# Leddriver.net
KiCad netlist of a schematic drawn in Altium Designer
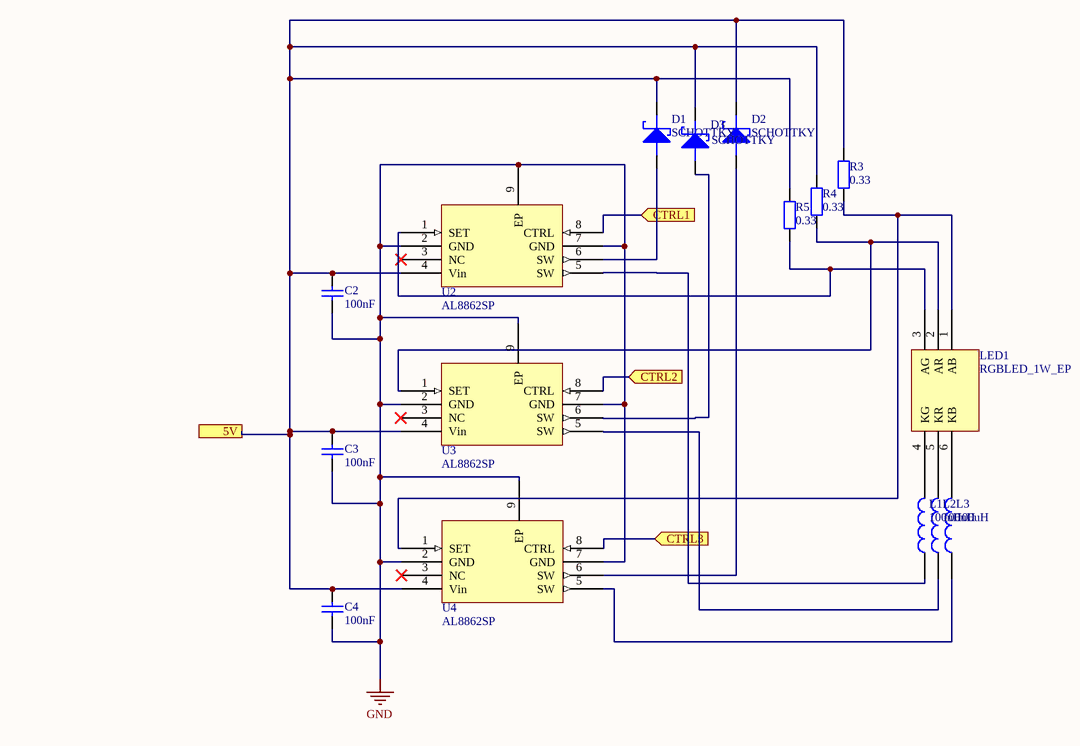
[diagram p0: Leddriver.SchDoc]

(export (version "E")
  (design (tool "Eeschema 10.0.6"))
  (components
    (comp (ref "C2")
      (value "100nF")
      (footprint "FP_0805_CAP_085")
      (description "Capacitor")
      (libsource (lib "hallglib") (part "CAP"))
    )
    (comp (ref "C3")
      (value "100nF")
      (footprint "FP_0805_CAP_085")
      (description "Capacitor")
      (libsource (lib "hallglib") (part "CAP"))
    )
    (comp (ref "C4")
      (value "100nF")
      (footprint "FP_0805_CAP_085")
      (description "Capacitor")
      (libsource (lib "hallglib") (part "CAP"))
    )
    (comp (ref "D1")
      (value "SCHOTTKY")
      (footprint "FP_SOD-123")
      (description "Schottky diode")
      (libsource (lib "hallglib") (part "SCHOTTKY"))
    )
    (comp (ref "D2")
      (value "SCHOTTKY")
      (footprint "FP_SOD-123")
      (description "Schottky diode")
      (libsource (lib "hallglib") (part "SCHOTTKY"))
    )
    (comp (ref "D3")
      (value "SCHOTTKY")
      (footprint "FP_SOD-123")
      (description "Schottky diode")
      (libsource (lib "hallglib") (part "SCHOTTKY"))
    )
    (comp (ref "L1")
      (value "100uH")
      (footprint "INDP5350X45N")
      (description "Inductor")
      (libsource (lib "hallglib") (part "IND"))
    )
    (comp (ref "L2")
      (value "100uH")
      (footprint "INDP5350X45N")
      (description "Inductor")
      (libsource (lib "hallglib") (part "IND"))
    )
    (comp (ref "L3")
      (value "100uH")
      (footprint "INDP5350X45N")
      (description "Inductor")
      (libsource (lib "hallglib") (part "IND"))
    )
    (comp (ref "LED1")
      (value "RGBLED_1W_EP")
      (footprint "RGBLED_1W_EP")
      (libsource (lib "hallglib") (part "RGBLED_1W_EP"))
    )
    (comp (ref "R3")
      (value "0.33")
      (footprint "FP_0805_RES")
      (description "Resistor")
      (fields (field (name "Comment") "0.22"))
      (libsource (lib "hallglib") (part "RES"))
    )
    (comp (ref "R4")
      (value "0.33")
      (footprint "FP_0805_RES")
      (description "Resistor")
      (fields (field (name "Comment") "0.22"))
      (libsource (lib "hallglib") (part "RES"))
    )
    (comp (ref "R5")
      (value "0.33")
      (footprint "FP_0805_RES")
      (description "Resistor")
      (fields (field (name "Comment") "0.22"))
      (libsource (lib "hallglib") (part "RES"))
    )
    (comp (ref "U2")
      (value "AL8862SP")
      (footprint "SOIC127P600-8N_LEd_Driver")
      (libsource (lib "") (part "AL8862SP_1"))
    )
    (comp (ref "U3")
      (value "AL8862SP")
      (footprint "SOIC127P600-8N_LEd_Driver")
      (libsource (lib "hallglib") (part "AL8862SP"))
    )
    (comp (ref "U4")
      (value "AL8862SP")
      (footprint "SOIC127P600-8N_LEd_Driver")
      (libsource (lib "hallglib") (part "AL8862SP"))
    )
  )
  (nets
    (net (code "1") (name "/5V") (class "Default")
      (node (ref "C2") (pin "2") (pinfunction "2_2") (pintype "passive"))
      (node (ref "C3") (pin "2") (pinfunction "2_2") (pintype "passive"))
      (node (ref "C4") (pin "2") (pinfunction "2_2") (pintype "passive"))
      (node (ref "D1") (pin "2") (pinfunction "CATHODE_2") (pintype "passive"))
      (node (ref "D2") (pin "2") (pinfunction "CATHODE_2") (pintype "passive"))
      (node (ref "D3") (pin "2") (pinfunction "CATHODE_2") (pintype "passive"))
      (node (ref "R3") (pin "2") (pinfunction "2_2") (pintype "passive"))
      (node (ref "R4") (pin "2") (pinfunction "2_2") (pintype "passive"))
      (node (ref "R5") (pin "2") (pinfunction "2_2") (pintype "passive"))
      (node (ref "U2") (pin "4") (pinfunction "Vin_4") (pintype "power_in"))
      (node (ref "U3") (pin "4") (pinfunction "Vin_4") (pintype "power_in"))
      (node (ref "U4") (pin "4") (pinfunction "Vin_4") (pintype "power_in"))
    )
    (net (code "2") (name "/CTRL1") (class "Default")
      (node (ref "U2") (pin "8") (pinfunction "CTRL_8") (pintype "input"))
    )
    (net (code "3") (name "/CTRL2") (class "Default")
      (node (ref "U3") (pin "8") (pinfunction "CTRL_8") (pintype "input"))
    )
    (net (code "4") (name "/CTRL3") (class "Default")
      (node (ref "U4") (pin "8") (pinfunction "CTRL_8") (pintype "input"))
    )
    (net (code "5") (name "GND") (class "Default")
      (node (ref "C2") (pin "1") (pinfunction "1_1") (pintype "passive"))
      (node (ref "C3") (pin "1") (pinfunction "1_1") (pintype "passive"))
      (node (ref "C4") (pin "1") (pinfunction "1_1") (pintype "passive"))
      (node (ref "U2") (pin "2") (pinfunction "GND_2") (pintype "power_in"))
      (node (ref "U2") (pin "7") (pinfunction "GND_7") (pintype "power_in"))
      (node (ref "U2") (pin "9") (pinfunction "EP_9") (pintype "power_in"))
      (node (ref "U3") (pin "2") (pinfunction "GND_2") (pintype "power_in"))
      (node (ref "U3") (pin "7") (pinfunction "GND_7") (pintype "power_in"))
      (node (ref "U3") (pin "9") (pinfunction "EP_9") (pintype "power_in"))
      (node (ref "U4") (pin "2") (pinfunction "GND_2") (pintype "power_in"))
      (node (ref "U4") (pin "7") (pinfunction "GND_7") (pintype "power_in"))
      (node (ref "U4") (pin "9") (pinfunction "EP_9") (pintype "power_in"))
    )
    (net (code "6") (name "Net-(D1-ANODE)") (class "Default")
      (node (ref "D1") (pin "1") (pinfunction "ANODE_1") (pintype "passive"))
      (node (ref "U2") (pin "6") (pinfunction "SW_6") (pintype "output"))
    )
    (net (code "7") (name "Net-(D2-ANODE)") (class "Default")
      (node (ref "D2") (pin "1") (pinfunction "ANODE_1") (pintype "passive"))
      (node (ref "U4") (pin "6") (pinfunction "SW_6") (pintype "output"))
    )
    (net (code "8") (name "Net-(D3-ANODE)") (class "Default")
      (node (ref "D3") (pin "1") (pinfunction "ANODE_1") (pintype "passive"))
      (node (ref "U3") (pin "6") (pinfunction "SW_6") (pintype "output"))
    )
    (net (code "9") (name "Net-(L1-Pad1)") (class "Default")
      (node (ref "L1") (pin "1") (pinfunction "1_1") (pintype "passive"))
      (node (ref "U2") (pin "5") (pinfunction "SW_5") (pintype "output"))
    )
    (net (code "10") (name "Net-(L2-Pad1)") (class "Default")
      (node (ref "L2") (pin "1") (pinfunction "1_1") (pintype "passive"))
      (node (ref "U3") (pin "5") (pinfunction "SW_5") (pintype "output"))
    )
    (net (code "11") (name "Net-(L3-Pad1)") (class "Default")
      (node (ref "L3") (pin "1") (pinfunction "1_1") (pintype "passive"))
      (node (ref "U4") (pin "5") (pinfunction "SW_5") (pintype "output"))
    )
    (net (code "12") (name "Net-(LED1-AB)") (class "Default")
      (node (ref "LED1") (pin "1") (pinfunction "AB_1") (pintype "passive"))
      (node (ref "R3") (pin "1") (pinfunction "1_1") (pintype "passive"))
      (node (ref "U4") (pin "1") (pinfunction "SET_1") (pintype "input"))
    )
    (net (code "13") (name "Net-(LED1-AG)") (class "Default")
      (node (ref "LED1") (pin "3") (pinfunction "AG_3") (pintype "passive"))
      (node (ref "R5") (pin "1") (pinfunction "1_1") (pintype "passive"))
      (node (ref "U2") (pin "1") (pinfunction "SET_1") (pintype "input"))
    )
    (net (code "14") (name "Net-(LED1-AR)") (class "Default")
      (node (ref "LED1") (pin "2") (pinfunction "AR_2") (pintype "passive"))
      (node (ref "R4") (pin "1") (pinfunction "1_1") (pintype "passive"))
      (node (ref "U3") (pin "1") (pinfunction "SET_1") (pintype "input"))
    )
    (net (code "15") (name "Net-(LED1-KB)") (class "Default")
      (node (ref "L3") (pin "2") (pinfunction "2_2") (pintype "passive"))
      (node (ref "LED1") (pin "6") (pinfunction "KB_6") (pintype "passive"))
    )
    (net (code "16") (name "Net-(LED1-KG)") (class "Default")
      (node (ref "L1") (pin "2") (pinfunction "2_2") (pintype "passive"))
      (node (ref "LED1") (pin "4") (pinfunction "KG_4") (pintype "passive"))
    )
    (net (code "17") (name "Net-(LED1-KR)") (class "Default")
      (node (ref "L2") (pin "2") (pinfunction "2_2") (pintype "passive"))
      (node (ref "LED1") (pin "5") (pinfunction "KR_5") (pintype "passive"))
    )
    (net (code "18") (name "unconnected-(U2-NC-Pad3)") (class "Default")
      (node (ref "U2") (pin "3") (pinfunction "NC_3") (pintype "passive+no_connect"))
    )
    (net (code "19") (name "unconnected-(U3-NC-Pad3)") (class "Default")
      (node (ref "U3") (pin "3") (pinfunction "NC_3") (pintype "passive+no_connect"))
    )
    (net (code "20") (name "unconnected-(U4-NC-Pad3)") (class "Default")
      (node (ref "U4") (pin "3") (pinfunction "NC_3") (pintype "passive+no_connect"))
    )
  )
)
